# SCH_Usb-Hub_2024-07-29.net
KiCad netlist of a schematic drawn in EasyEDA
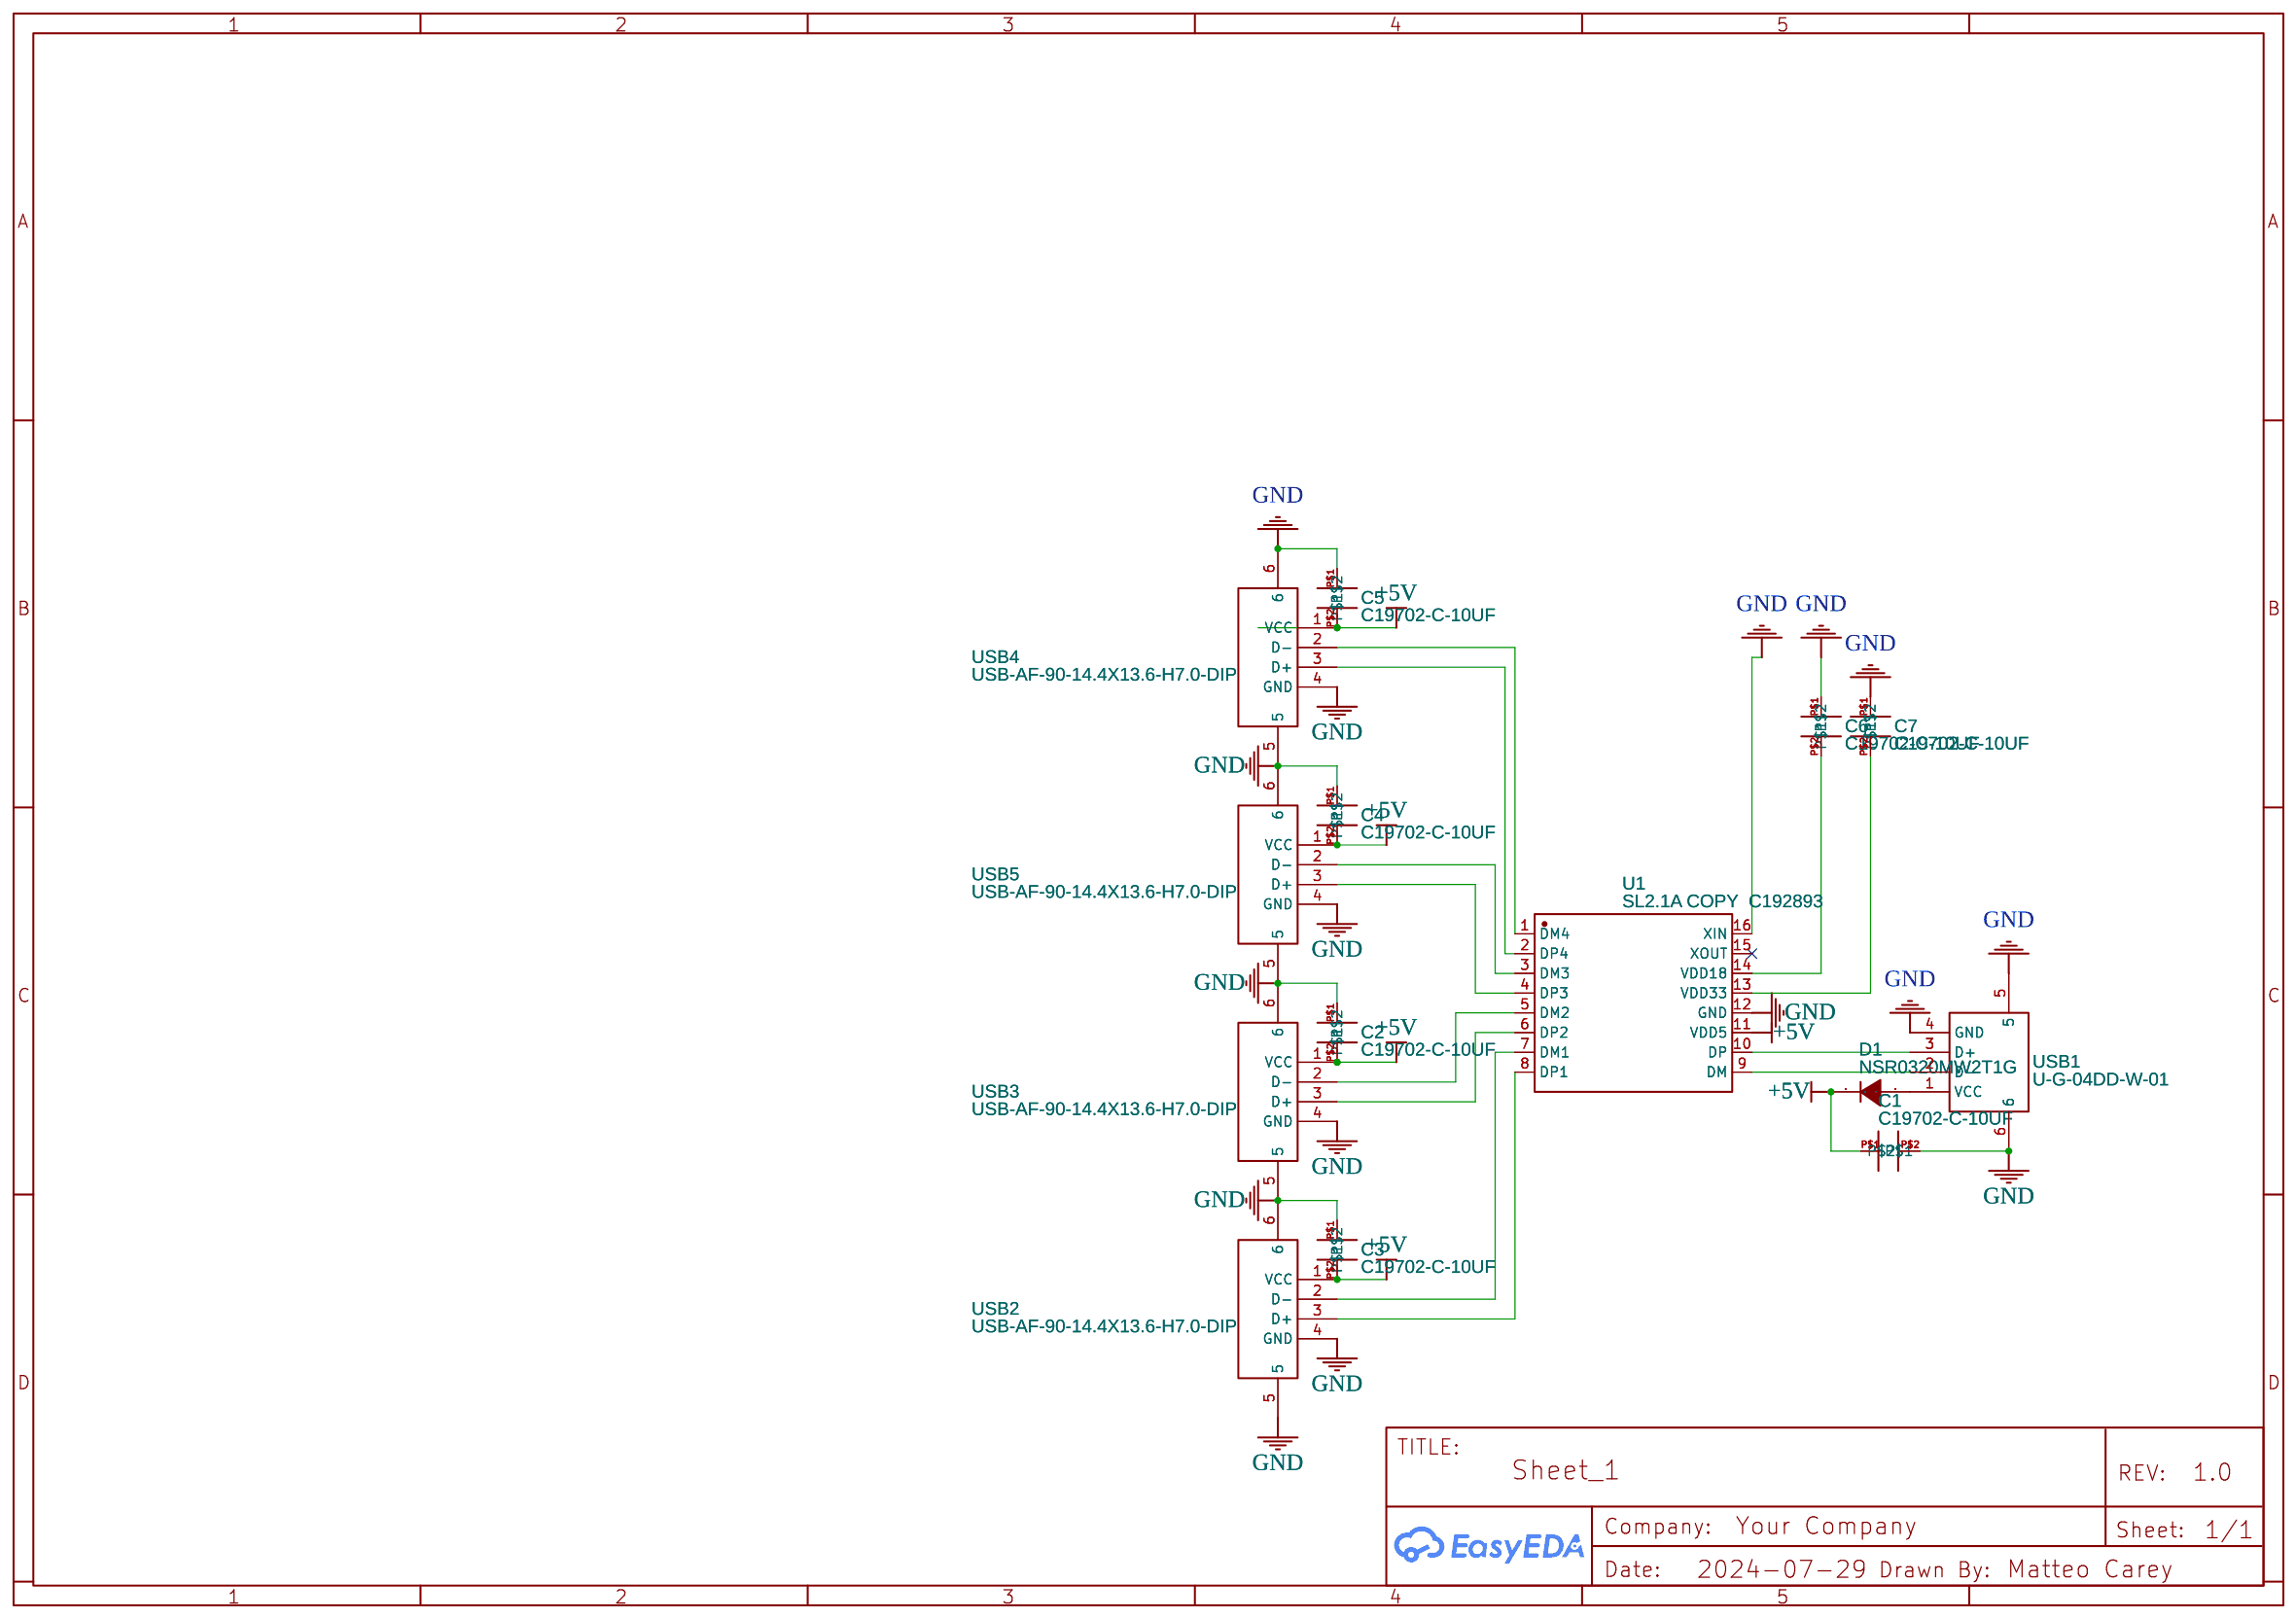
[diagram p0: schematic sheet]

(export (version "E")
  (design (tool "Eeschema 10.0.6"))
  (components
    (comp (ref "C1") (value "C19702-C-10UF") (libsource (lib "") (part "C19702-C-10UF_1")))
    (comp (ref "C2") (value "C19702-C-10UF") (libsource (lib "") (part "C19702-C-10UF")))
    (comp (ref "C3") (value "C19702-C-10UF") (libsource (lib "") (part "C19702-C-10UF")))
    (comp (ref "C4") (value "C19702-C-10UF") (libsource (lib "") (part "C19702-C-10UF")))
    (comp (ref "C5") (value "C19702-C-10UF") (libsource (lib "") (part "C19702-C-10UF")))
    (comp (ref "C6") (value "C19702-C-10UF") (libsource (lib "") (part "C19702-C-10UF")))
    (comp (ref "C7") (value "C19702-C-10UF") (libsource (lib "") (part "C19702-C-10UF")))
    (comp (ref "D1")
      (value "NSR0320MW2T1G")
      (fields (field (name "Manufacturer") "onsemi(安森美)"))
      (libsource (lib "") (part "NSR0320MW2T1G"))
    )
    (comp (ref "U1")
      (value "SL2.1A COPY  C192893")
      (fields (field (name "Manufacturer Part") "SL2.1A") (field (name "Manufacturer") "CoreChips(和芯润德)"))
      (libsource (lib "") (part "SL2.1A COPY  C192893"))
    )
    (comp (ref "USB1")
      (value "U-G-04DD-W-01")
      (fields (field (name "Manufacturer Part") "U-G-O4DD-W-1") (field (name "Manufacturer") "韩国韩荣"))
      (libsource (lib "") (part "U-G-04DD-W-01"))
    )
    (comp (ref "USB2")
      (value "USB-AF-90-14.4X13.6-H7.0-DIP")
      (fields (field (name "Manufacturer Part") "903-131A1011D10100") (field (name "Manufacturer") "精拓金"))
      (libsource (lib "") (part "USB-AF-90-14.4X13.6-H7.0-DIP"))
    )
    (comp (ref "USB3")
      (value "USB-AF-90-14.4X13.6-H7.0-DIP")
      (fields (field (name "Manufacturer Part") "903-131A1011D10100") (field (name "Manufacturer") "精拓金"))
      (libsource (lib "") (part "USB-AF-90-14.4X13.6-H7.0-DIP"))
    )
    (comp (ref "USB4")
      (value "USB-AF-90-14.4X13.6-H7.0-DIP")
      (fields (field (name "Manufacturer Part") "903-131A1011D10100") (field (name "Manufacturer") "精拓金"))
      (libsource (lib "") (part "USB-AF-90-14.4X13.6-H7.0-DIP"))
    )
    (comp (ref "USB5")
      (value "USB-AF-90-14.4X13.6-H7.0-DIP")
      (fields (field (name "Manufacturer Part") "903-131A1011D10100") (field (name "Manufacturer") "精拓金"))
      (libsource (lib "") (part "USB-AF-90-14.4X13.6-H7.0-DIP"))
    )
  )
  (nets
    (net (code "1") (name "+5V") (class "Default")
      (node (ref "C1") (pin "P$1") (pinfunction "P$1_P$1") (pintype "bidirectional"))
      (node (ref "C2") (pin "P$2") (pinfunction "P$2_P$2") (pintype "bidirectional"))
      (node (ref "C3") (pin "P$2") (pinfunction "P$2_P$2") (pintype "bidirectional"))
      (node (ref "C4") (pin "P$2") (pinfunction "P$2_P$2") (pintype "bidirectional"))
      (node (ref "C5") (pin "P$2") (pinfunction "P$2_P$2") (pintype "bidirectional"))
      (node (ref "D1") (pin "1") (pinfunction "C_1") (pintype "unspecified"))
      (node (ref "U1") (pin "11") (pinfunction "VDD5_11") (pintype "unspecified"))
      (node (ref "USB2") (pin "1") (pinfunction "VCC_1") (pintype "unspecified"))
      (node (ref "USB3") (pin "1") (pinfunction "VCC_1") (pintype "unspecified"))
      (node (ref "USB4") (pin "1") (pinfunction "VCC_1") (pintype "unspecified"))
      (node (ref "USB5") (pin "1") (pinfunction "VCC_1") (pintype "unspecified"))
    )
    (net (code "2") (name "GND") (class "Default")
      (node (ref "C1") (pin "P$2") (pinfunction "P$2_P$2") (pintype "bidirectional"))
      (node (ref "C2") (pin "P$1") (pinfunction "P$1_P$1") (pintype "bidirectional"))
      (node (ref "C3") (pin "P$1") (pinfunction "P$1_P$1") (pintype "bidirectional"))
      (node (ref "C4") (pin "P$1") (pinfunction "P$1_P$1") (pintype "bidirectional"))
      (node (ref "C5") (pin "P$1") (pinfunction "P$1_P$1") (pintype "bidirectional"))
      (node (ref "C6") (pin "P$1") (pinfunction "P$1_P$1") (pintype "bidirectional"))
      (node (ref "C7") (pin "P$1") (pinfunction "P$1_P$1") (pintype "bidirectional"))
      (node (ref "U1") (pin "12") (pinfunction "GND_12") (pintype "unspecified"))
      (node (ref "U1") (pin "16") (pinfunction "XIN_16") (pintype "unspecified"))
      (node (ref "USB1") (pin "4") (pinfunction "GND_4") (pintype "unspecified"))
      (node (ref "USB1") (pin "5") (pinfunction "5_5") (pintype "unspecified"))
      (node (ref "USB1") (pin "6") (pinfunction "6_6") (pintype "unspecified"))
      (node (ref "USB2") (pin "4") (pinfunction "GND_4") (pintype "unspecified"))
      (node (ref "USB2") (pin "5") (pinfunction "5_5") (pintype "unspecified"))
      (node (ref "USB2") (pin "6") (pinfunction "6_6") (pintype "unspecified"))
      (node (ref "USB3") (pin "4") (pinfunction "GND_4") (pintype "unspecified"))
      (node (ref "USB3") (pin "5") (pinfunction "5_5") (pintype "unspecified"))
      (node (ref "USB3") (pin "6") (pinfunction "6_6") (pintype "unspecified"))
      (node (ref "USB4") (pin "4") (pinfunction "GND_4") (pintype "unspecified"))
      (node (ref "USB4") (pin "5") (pinfunction "5_5") (pintype "unspecified"))
      (node (ref "USB4") (pin "6") (pinfunction "6_6") (pintype "unspecified"))
      (node (ref "USB5") (pin "4") (pinfunction "GND_4") (pintype "unspecified"))
      (node (ref "USB5") (pin "5") (pinfunction "5_5") (pintype "unspecified"))
      (node (ref "USB5") (pin "6") (pinfunction "6_6") (pintype "unspecified"))
    )
    (net (code "3") (name "Net-(D1-A)") (class "Default")
      (node (ref "D1") (pin "2") (pinfunction "A_2") (pintype "unspecified"))
      (node (ref "USB1") (pin "1") (pinfunction "VCC_1") (pintype "unspecified"))
    )
    (net (code "4") (name "Net-(U1-DM)") (class "Default")
      (node (ref "U1") (pin "9") (pinfunction "DM_9") (pintype "unspecified"))
      (node (ref "USB1") (pin "2") (pinfunction "D-_2") (pintype "unspecified"))
    )
    (net (code "5") (name "Net-(U1-DM1)") (class "Default")
      (node (ref "U1") (pin "7") (pinfunction "DM1_7") (pintype "unspecified"))
      (node (ref "USB2") (pin "2") (pinfunction "D-_2") (pintype "unspecified"))
    )
    (net (code "6") (name "Net-(U1-DM2)") (class "Default")
      (node (ref "U1") (pin "5") (pinfunction "DM2_5") (pintype "unspecified"))
      (node (ref "USB3") (pin "2") (pinfunction "D-_2") (pintype "unspecified"))
    )
    (net (code "7") (name "Net-(U1-DM3)") (class "Default")
      (node (ref "U1") (pin "3") (pinfunction "DM3_3") (pintype "unspecified"))
      (node (ref "USB5") (pin "2") (pinfunction "D-_2") (pintype "unspecified"))
    )
    (net (code "8") (name "Net-(U1-DM4)") (class "Default")
      (node (ref "U1") (pin "1") (pinfunction "DM4_1") (pintype "unspecified"))
      (node (ref "USB4") (pin "2") (pinfunction "D-_2") (pintype "unspecified"))
    )
    (net (code "9") (name "Net-(U1-DP)") (class "Default")
      (node (ref "U1") (pin "10") (pinfunction "DP_10") (pintype "unspecified"))
      (node (ref "USB1") (pin "3") (pinfunction "D+_3") (pintype "unspecified"))
    )
    (net (code "10") (name "Net-(U1-DP1)") (class "Default")
      (node (ref "U1") (pin "8") (pinfunction "DP1_8") (pintype "unspecified"))
      (node (ref "USB2") (pin "3") (pinfunction "D+_3") (pintype "unspecified"))
    )
    (net (code "11") (name "Net-(U1-DP2)") (class "Default")
      (node (ref "U1") (pin "6") (pinfunction "DP2_6") (pintype "unspecified"))
      (node (ref "USB3") (pin "3") (pinfunction "D+_3") (pintype "unspecified"))
    )
    (net (code "12") (name "Net-(U1-DP3)") (class "Default")
      (node (ref "U1") (pin "4") (pinfunction "DP3_4") (pintype "unspecified"))
      (node (ref "USB5") (pin "3") (pinfunction "D+_3") (pintype "unspecified"))
    )
    (net (code "13") (name "Net-(U1-DP4)") (class "Default")
      (node (ref "U1") (pin "2") (pinfunction "DP4_2") (pintype "unspecified"))
      (node (ref "USB4") (pin "3") (pinfunction "D+_3") (pintype "unspecified"))
    )
    (net (code "14") (name "Net-(U1-VDD18)") (class "Default")
      (node (ref "C6") (pin "P$2") (pinfunction "P$2_P$2") (pintype "bidirectional"))
      (node (ref "U1") (pin "14") (pinfunction "VDD18_14") (pintype "unspecified"))
    )
    (net (code "15") (name "Net-(U1-VDD33)") (class "Default")
      (node (ref "C7") (pin "P$2") (pinfunction "P$2_P$2") (pintype "bidirectional"))
      (node (ref "U1") (pin "13") (pinfunction "VDD33_13") (pintype "unspecified"))
    )
    (net (code "16") (name "unconnected-(U1-XOUT-Pad15)") (class "Default")
      (node (ref "U1") (pin "15") (pinfunction "XOUT_15") (pintype "unspecified+no_connect"))
    )
  )
)
